# force_sensor_pcb_v2.net
KiCad netlist of a schematic drawn in EAGLE
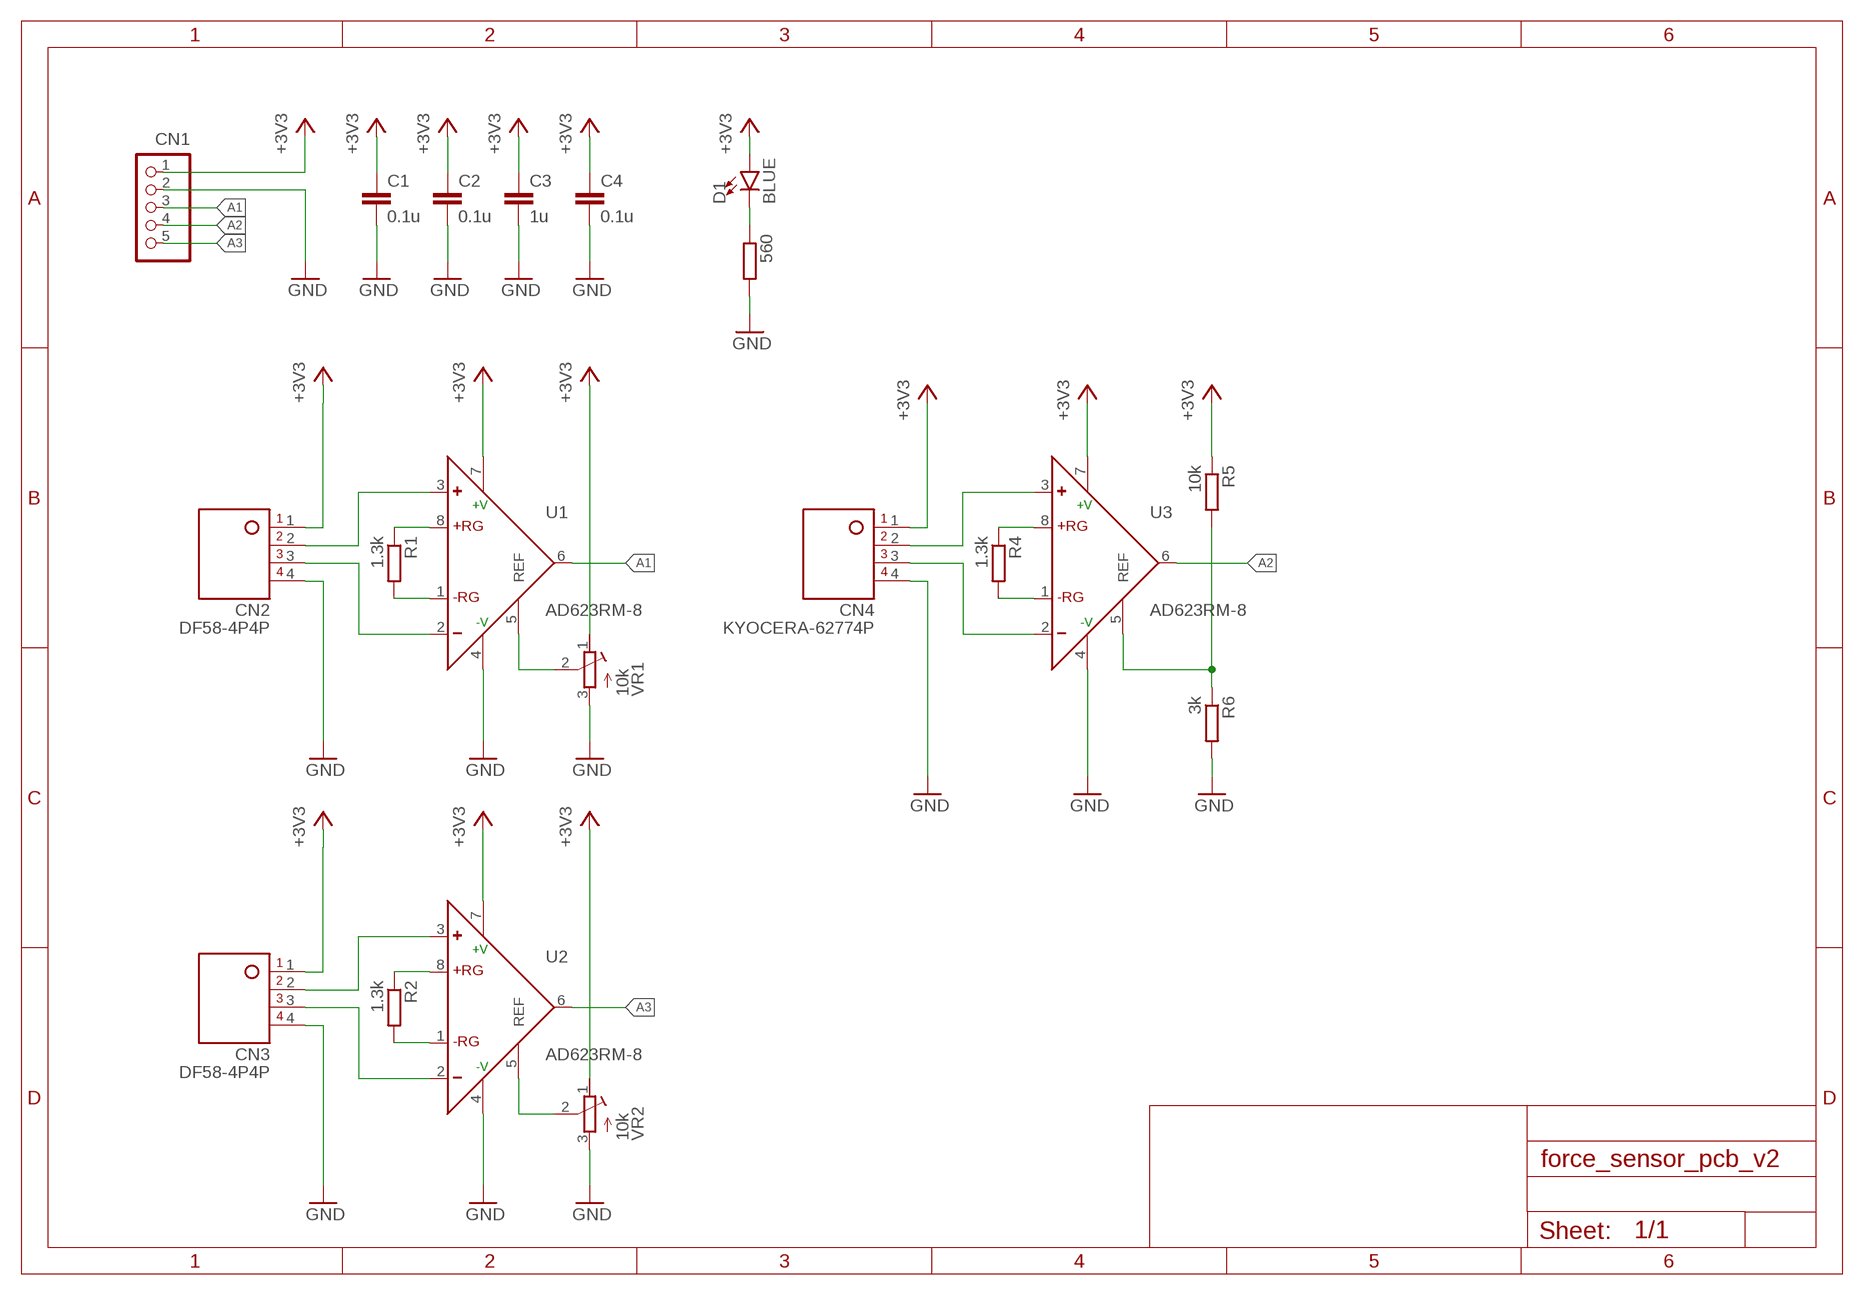
[diagram p0: schematic, sheet 1]

(export (version "E")
  (design (tool "Eeschema 10.0.6"))
  (components
    (comp (ref "560")
      (value "R-EU_R0603")
      (footprint "eagle-import:R0603")
      (libsource (lib "eagle-import") (part "R-EU_R0603"))
    )
    (comp (ref "C1")
      (value "0.1u")
      (footprint "eagle-import:C0603")
      (libsource (lib "eagle-import") (part "C-EUC0603"))
    )
    (comp (ref "C2")
      (value "0.1u")
      (footprint "eagle-import:C0603")
      (libsource (lib "eagle-import") (part "C-EUC0603"))
    )
    (comp (ref "C3")
      (value "1u")
      (footprint "eagle-import:C0603")
      (libsource (lib "eagle-import") (part "C-EUC0603"))
    )
    (comp (ref "C4")
      (value "0.1u")
      (footprint "eagle-import:C0603")
      (libsource (lib "eagle-import") (part "C-EUC0603"))
    )
    (comp (ref "CN1")
      (value "B5B-PH-K-S")
      (footprint "eagle-import:B5B-PH-K-S")
      (libsource (lib "eagle-import") (part "B5B-PH-K-S"))
    )
    (comp (ref "CN2")
      (value "DF58-4P4P")
      (footprint "eagle-import:DF58-4P")
      (libsource (lib "eagle-import") (part "DF58-4P4P"))
    )
    (comp (ref "CN3")
      (value "DF58-4P4P")
      (footprint "eagle-import:DF58-4P")
      (libsource (lib "eagle-import") (part "DF58-4P4P"))
    )
    (comp (ref "CN4")
      (value "KYOCERA-62774P")
      (footprint "eagle-import:KYOCERA-6277-4")
      (libsource (lib "eagle-import") (part "KYOCERA-62774P"))
    )
    (comp (ref "D1")
      (value "BLUE")
      (footprint "eagle-import:LED-0603")
      (libsource (lib "eagle-import") (part "LED-BLUE0603"))
    )
    (comp (ref "R1")
      (value "1.3k")
      (footprint "eagle-import:R0603")
      (libsource (lib "eagle-import") (part "R-EU_R0603"))
    )
    (comp (ref "R2")
      (value "1.3k")
      (footprint "eagle-import:R0603")
      (libsource (lib "eagle-import") (part "R-EU_R0603"))
    )
    (comp (ref "R4")
      (value "1.3k")
      (footprint "eagle-import:R0603")
      (libsource (lib "eagle-import") (part "R-EU_R0603"))
    )
    (comp (ref "R5")
      (value "10k")
      (footprint "eagle-import:R0603")
      (libsource (lib "eagle-import") (part "R-EU_R0603"))
    )
    (comp (ref "R6")
      (value "3k")
      (footprint "eagle-import:R0603")
      (libsource (lib "eagle-import") (part "R-EU_R0603"))
    )
    (comp (ref "U1")
      (value "AD623RM-8")
      (footprint "eagle-import:MSOP08")
      (libsource (lib "eagle-import") (part "AD623RM-8"))
    )
    (comp (ref "U2")
      (value "AD623RM-8")
      (footprint "eagle-import:MSOP08")
      (libsource (lib "eagle-import") (part "AD623RM-8"))
    )
    (comp (ref "U3")
      (value "AD623RM-8")
      (footprint "eagle-import:MSOP08")
      (libsource (lib "eagle-import") (part "AD623RM-8"))
    )
    (comp (ref "VR1")
      (value "10k")
      (footprint "eagle-import:D43A")
      (libsource (lib "eagle-import") (part "D43A"))
    )
    (comp (ref "VR2")
      (value "10k")
      (footprint "eagle-import:D43A")
      (libsource (lib "eagle-import") (part "D43A"))
    )
  )
  (nets
    (net (code "1") (name "+3V3") (class "Default")
      (node (ref "C1") (pin "1") (pinfunction "1_1") (pintype "passive"))
      (node (ref "C2") (pin "1") (pinfunction "1_1") (pintype "passive"))
      (node (ref "C3") (pin "1") (pinfunction "1_1") (pintype "passive"))
      (node (ref "C4") (pin "1") (pinfunction "1_1") (pintype "passive"))
      (node (ref "CN1") (pin "1") (pinfunction "1_1") (pintype "passive"))
      (node (ref "CN2") (pin "1") (pinfunction "1_1") (pintype "bidirectional"))
      (node (ref "CN3") (pin "1") (pinfunction "1_1") (pintype "bidirectional"))
      (node (ref "CN4") (pin "1") (pinfunction "1_1") (pintype "bidirectional"))
      (node (ref "D1") (pin "A") (pinfunction "A_A") (pintype "passive"))
      (node (ref "R5") (pin "1") (pinfunction "1_1") (pintype "passive"))
      (node (ref "U1") (pin "7") (pinfunction "+V_7") (pintype "power_in"))
      (node (ref "U2") (pin "7") (pinfunction "+V_7") (pintype "power_in"))
      (node (ref "U3") (pin "7") (pinfunction "+V_7") (pintype "power_in"))
      (node (ref "VR1") (pin "1") (pinfunction "1_1") (pintype "passive"))
      (node (ref "VR2") (pin "1") (pinfunction "1_1") (pintype "passive"))
    )
    (net (code "2") (name "A1") (class "Default")
      (node (ref "CN1") (pin "3") (pinfunction "3_3") (pintype "passive"))
      (node (ref "U1") (pin "6") (pinfunction "OUT_6") (pintype "output"))
    )
    (net (code "3") (name "A2") (class "Default")
      (node (ref "CN1") (pin "4") (pinfunction "4_4") (pintype "passive"))
      (node (ref "U3") (pin "6") (pinfunction "OUT_6") (pintype "output"))
    )
    (net (code "4") (name "A3") (class "Default")
      (node (ref "CN1") (pin "5") (pinfunction "5_5") (pintype "passive"))
      (node (ref "U2") (pin "6") (pinfunction "OUT_6") (pintype "output"))
    )
    (net (code "5") (name "GND") (class "Default")
      (node (ref "560") (pin "2") (pinfunction "2_2") (pintype "passive"))
      (node (ref "C1") (pin "2") (pinfunction "2_2") (pintype "passive"))
      (node (ref "C2") (pin "2") (pinfunction "2_2") (pintype "passive"))
      (node (ref "C3") (pin "2") (pinfunction "2_2") (pintype "passive"))
      (node (ref "C4") (pin "2") (pinfunction "2_2") (pintype "passive"))
      (node (ref "CN1") (pin "2") (pinfunction "2_2") (pintype "passive"))
      (node (ref "CN2") (pin "4") (pinfunction "4_4") (pintype "bidirectional"))
      (node (ref "CN3") (pin "4") (pinfunction "4_4") (pintype "bidirectional"))
      (node (ref "CN4") (pin "4") (pinfunction "4_4") (pintype "bidirectional"))
      (node (ref "R6") (pin "2") (pinfunction "2_2") (pintype "passive"))
      (node (ref "U1") (pin "4") (pinfunction "-V_4") (pintype "power_in"))
      (node (ref "U2") (pin "4") (pinfunction "-V_4") (pintype "power_in"))
      (node (ref "U3") (pin "4") (pinfunction "-V_4") (pintype "power_in"))
      (node (ref "VR1") (pin "3") (pinfunction "3_3") (pintype "passive"))
      (node (ref "VR2") (pin "3") (pinfunction "3_3") (pintype "passive"))
    )
    (net (code "6") (name "Net-(560-Pad1)") (class "Default")
      (node (ref "560") (pin "1") (pinfunction "1_1") (pintype "passive"))
      (node (ref "D1") (pin "C") (pinfunction "C_C") (pintype "passive"))
    )
    (net (code "7") (name "Net-(U1-+IN)") (class "Default")
      (node (ref "CN2") (pin "2") (pinfunction "2_2") (pintype "bidirectional"))
      (node (ref "U1") (pin "3") (pinfunction "+IN_3") (pintype "input"))
    )
    (net (code "8") (name "Net-(U1-+RG)") (class "Default")
      (node (ref "R1") (pin "1") (pinfunction "1_1") (pintype "passive"))
      (node (ref "U1") (pin "8") (pinfunction "+RG_8") (pintype "passive"))
    )
    (net (code "9") (name "Net-(U1--IN)") (class "Default")
      (node (ref "CN2") (pin "3") (pinfunction "3_3") (pintype "bidirectional"))
      (node (ref "U1") (pin "2") (pinfunction "-IN_2") (pintype "input"))
    )
    (net (code "10") (name "Net-(U1--RG)") (class "Default")
      (node (ref "R1") (pin "2") (pinfunction "2_2") (pintype "passive"))
      (node (ref "U1") (pin "1") (pinfunction "-RG_1") (pintype "passive"))
    )
    (net (code "11") (name "Net-(U1-REF)") (class "Default")
      (node (ref "U1") (pin "5") (pinfunction "REF_5") (pintype "passive"))
      (node (ref "VR1") (pin "2") (pinfunction "2_2") (pintype "passive"))
    )
    (net (code "12") (name "Net-(U2-+IN)") (class "Default")
      (node (ref "CN3") (pin "2") (pinfunction "2_2") (pintype "bidirectional"))
      (node (ref "U2") (pin "3") (pinfunction "+IN_3") (pintype "input"))
    )
    (net (code "13") (name "Net-(U2-+RG)") (class "Default")
      (node (ref "R2") (pin "1") (pinfunction "1_1") (pintype "passive"))
      (node (ref "U2") (pin "8") (pinfunction "+RG_8") (pintype "passive"))
    )
    (net (code "14") (name "Net-(U2--IN)") (class "Default")
      (node (ref "CN3") (pin "3") (pinfunction "3_3") (pintype "bidirectional"))
      (node (ref "U2") (pin "2") (pinfunction "-IN_2") (pintype "input"))
    )
    (net (code "15") (name "Net-(U2--RG)") (class "Default")
      (node (ref "R2") (pin "2") (pinfunction "2_2") (pintype "passive"))
      (node (ref "U2") (pin "1") (pinfunction "-RG_1") (pintype "passive"))
    )
    (net (code "16") (name "Net-(U2-REF)") (class "Default")
      (node (ref "U2") (pin "5") (pinfunction "REF_5") (pintype "passive"))
      (node (ref "VR2") (pin "2") (pinfunction "2_2") (pintype "passive"))
    )
    (net (code "17") (name "Net-(U3-+IN)") (class "Default")
      (node (ref "CN4") (pin "2") (pinfunction "2_2") (pintype "bidirectional"))
      (node (ref "U3") (pin "3") (pinfunction "+IN_3") (pintype "input"))
    )
    (net (code "18") (name "Net-(U3-+RG)") (class "Default")
      (node (ref "R4") (pin "1") (pinfunction "1_1") (pintype "passive"))
      (node (ref "U3") (pin "8") (pinfunction "+RG_8") (pintype "passive"))
    )
    (net (code "19") (name "Net-(U3--IN)") (class "Default")
      (node (ref "CN4") (pin "3") (pinfunction "3_3") (pintype "bidirectional"))
      (node (ref "U3") (pin "2") (pinfunction "-IN_2") (pintype "input"))
    )
    (net (code "20") (name "Net-(U3--RG)") (class "Default")
      (node (ref "R4") (pin "2") (pinfunction "2_2") (pintype "passive"))
      (node (ref "U3") (pin "1") (pinfunction "-RG_1") (pintype "passive"))
    )
    (net (code "21") (name "Net-(U3-REF)") (class "Default")
      (node (ref "R5") (pin "2") (pinfunction "2_2") (pintype "passive"))
      (node (ref "R6") (pin "1") (pinfunction "1_1") (pintype "passive"))
      (node (ref "U3") (pin "5") (pinfunction "REF_5") (pintype "passive"))
    )
  )
)
